# LED.net
KiCad netlist of a schematic drawn in Altium Designer
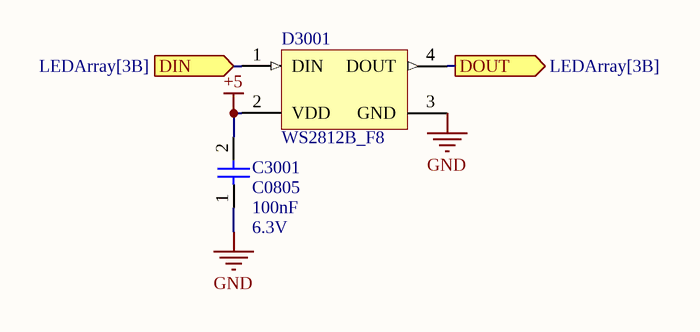
[diagram p0: LED.SchDoc]

(export (version "E")
  (design (tool "Eeschema 10.0.6"))
  (components
    (comp (ref "C3001")
      (value "C0805")
      (footprint "CC0805")
      (description "Capacitor")
      (fields
        (field (name "TOLERANCE") "±?%")
        (field (name "CAPACITANCE") "100nF")
        (field (name "VOLTAGE") "6.3V")
      )
      (libsource (lib "MyLibrary") (part "C0805"))
    )
    (comp (ref "D3001")
      (value "WS2812B_F8")
      (footprint "WS2812B_F8")
      (description "Addressable 8mm LED")
      (fields (field (name "VOLTAGE") "5V"))
      (libsource (lib "MyLibrary") (part "WS2812B_F8"))
    )
  )
  (nets
    (net (code "1") (name "+5") (class "Default")
      (node (ref "C3001") (pin "2") (pintype "passive"))
      (node (ref "D3001") (pin "2") (pinfunction "VDD_2") (pintype "power_in"))
    )
    (net (code "2") (name "/DIN") (class "Default")
      (node (ref "D3001") (pin "1") (pinfunction "DIN_1") (pintype "input"))
    )
    (net (code "3") (name "/DOUT") (class "Default")
      (node (ref "D3001") (pin "4") (pinfunction "DOUT_4") (pintype "output"))
    )
    (net (code "4") (name "GND") (class "Default")
      (node (ref "C3001") (pin "1") (pintype "passive"))
      (node (ref "D3001") (pin "3") (pinfunction "GND_3") (pintype "power_in"))
    )
  )
)
